# DRV8701E.net
KiCad netlist of a schematic drawn in Altium Designer
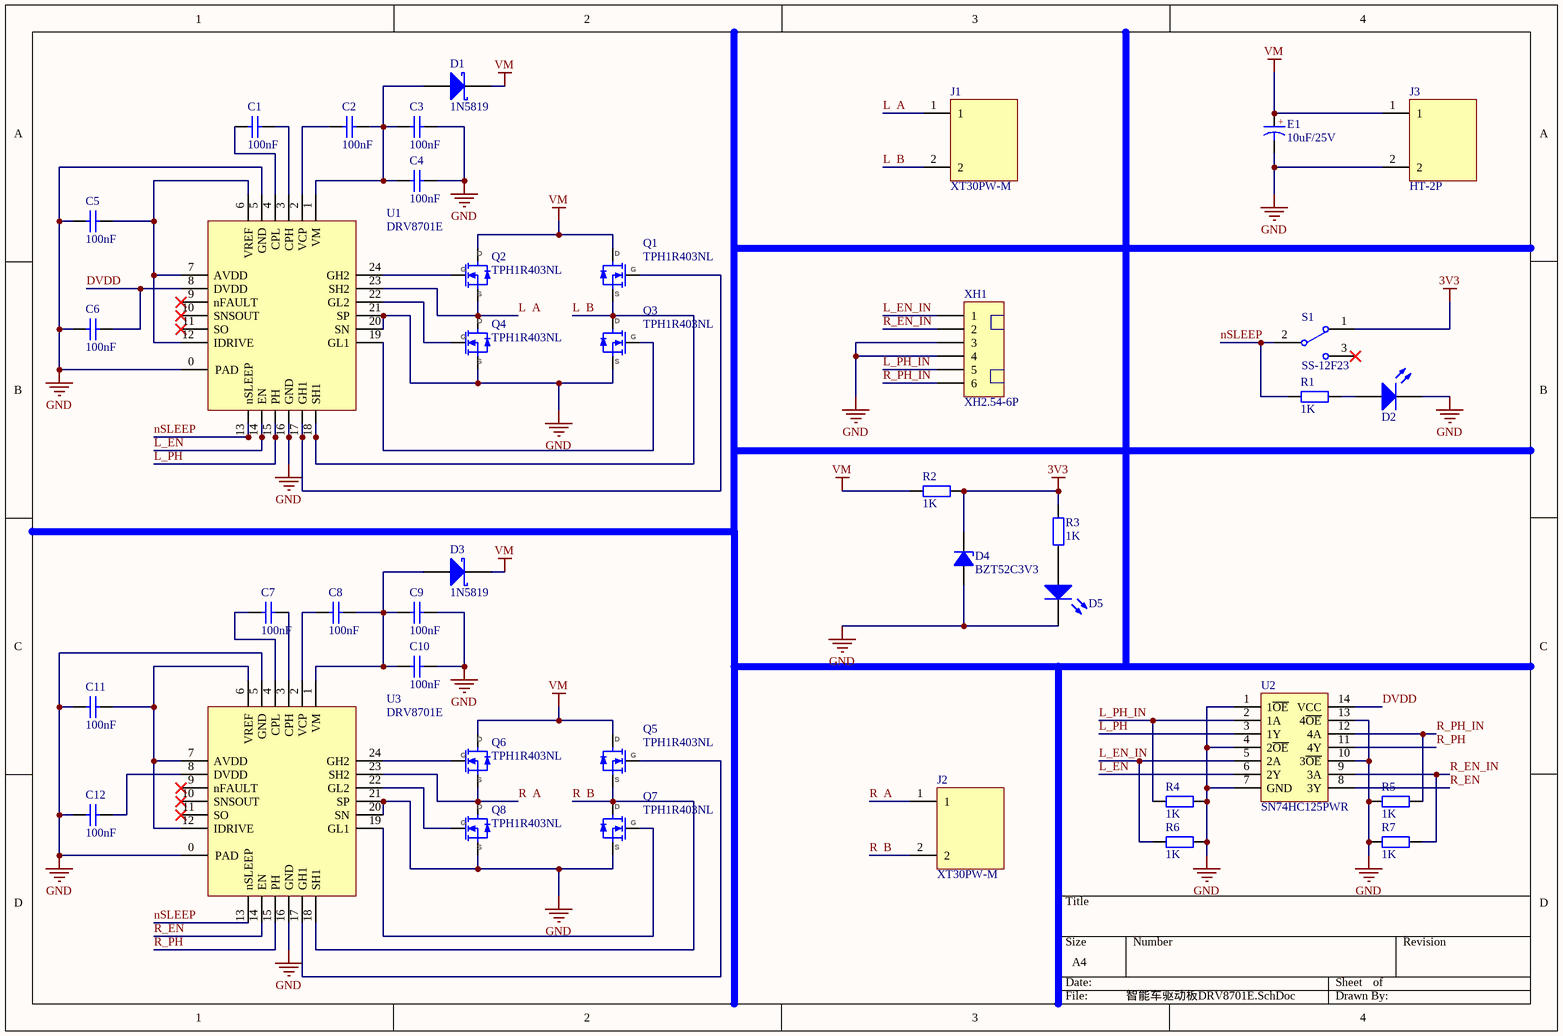
[diagram p0: 智能车驱动板DRV8701E.SchDoc]

(export (version "E")
  (design (tool "Eeschema 10.0.6"))
  (components
    (comp (ref "C1")
      (value "100nF")
      (footprint "C0603_L")
      (description "贴片电容")
      (libsource (lib "0.1_电容&电感&电阻&保险丝") (part "C-SMD"))
    )
    (comp (ref "C2")
      (value "100nF")
      (footprint "C0603_L")
      (description "贴片电容")
      (libsource (lib "0.1_电容&电感&电阻&保险丝") (part "C-SMD"))
    )
    (comp (ref "C3")
      (value "100nF")
      (footprint "C0603_L")
      (description "贴片电容")
      (libsource (lib "0.1_电容&电感&电阻&保险丝") (part "C-SMD"))
    )
    (comp (ref "C4")
      (value "100nF")
      (footprint "C0603_L")
      (description "贴片电容")
      (libsource (lib "0.1_电容&电感&电阻&保险丝") (part "C-SMD"))
    )
    (comp (ref "C5")
      (value "100nF")
      (footprint "C0603_L")
      (description "贴片电容")
      (libsource (lib "0.1_电容&电感&电阻&保险丝") (part "C-SMD"))
    )
    (comp (ref "C6")
      (value "100nF")
      (footprint "C0603_L")
      (description "贴片电容")
      (libsource (lib "0.1_电容&电感&电阻&保险丝") (part "C-SMD"))
    )
    (comp (ref "C7")
      (value "100nF")
      (footprint "C0603_L")
      (description "贴片电容")
      (libsource (lib "0.1_电容&电感&电阻&保险丝") (part "C-SMD"))
    )
    (comp (ref "C8")
      (value "100nF")
      (footprint "C0603_L")
      (description "贴片电容")
      (libsource (lib "0.1_电容&电感&电阻&保险丝") (part "C-SMD"))
    )
    (comp (ref "C9")
      (value "100nF")
      (footprint "C0603_L")
      (description "贴片电容")
      (libsource (lib "0.1_电容&电感&电阻&保险丝") (part "C-SMD"))
    )
    (comp (ref "C10")
      (value "100nF")
      (footprint "C0603_L")
      (description "贴片电容")
      (libsource (lib "0.1_电容&电感&电阻&保险丝") (part "C-SMD"))
    )
    (comp (ref "C11")
      (value "100nF")
      (footprint "C0603_L")
      (description "贴片电容")
      (libsource (lib "0.1_电容&电感&电阻&保险丝") (part "C-SMD"))
    )
    (comp (ref "C12")
      (value "100nF")
      (footprint "C0603_L")
      (description "贴片电容")
      (libsource (lib "0.1_电容&电感&电阻&保险丝") (part "C-SMD"))
    )
    (comp (ref "D1")
      (value "1N5819")
      (footprint "SOD-323")
      (description "肖特基二极管")
      (libsource (lib "0.2_二极管&整流桥") (part "1N5819"))
    )
    (comp (ref "D2")
      (value "LED")
      (footprint "LED-0603_R")
      (description "贴片发光二极管")
      (libsource (lib "0.3_LED发光二极管") (part "LED_SMD"))
    )
    (comp (ref "D3")
      (value "1N5819")
      (footprint "SOD-323")
      (description "肖特基二极管")
      (libsource (lib "0.2_二极管&整流桥") (part "1N5819"))
    )
    (comp (ref "D4")
      (value "BZT52C3V3")
      (footprint "SOD-123-L")
      (description "3.3V稳压二极管")
      (fields (field (name "PUBLISHER") "Altium Limited"))
      (libsource (lib "0.2_二极管&整流桥") (part "Diode Zen"))
    )
    (comp (ref "D5")
      (value "LED")
      (footprint "LED-0603_R")
      (description "贴片发光二极管")
      (libsource (lib "0.3_LED发光二极管") (part "LED_SMD"))
    )
    (comp (ref "E1")
      (value "10uF/25V")
      (footprint "CT-2.0*5*8-R")
      (description "直插固态电容")
      (libsource (lib "0.1_电容&电感&电阻&保险丝") (part "C-CS"))
    )
    (comp (ref "J1")
      (value "XT30PW-M")
      (footprint "XT30-WI")
      (description "30A Low Temperature Rise Fire Retardant Plug")
      (libsource (lib "5.12_XT30&XT60") (part "XT30PW-M"))
    )
    (comp (ref "J2")
      (value "XT30PW-M")
      (footprint "XT30-WI")
      (description "30A Low Temperature Rise Fire Retardant Plug")
      (libsource (lib "5.12_XT30&XT60") (part "XT30PW-M"))
    )
    (comp (ref "J3")
      (value "HT-2P")
      (footprint "CZ-5.08-L-Z-2P")
      (description "30A Low Temperature Rise Fire Retardant Plug")
      (fields (field (name "MANUFACTURER_PART_NUMBER") "XT30PW-M"))
      (libsource (lib "5.12_XT30&XT60") (part "XT30PW-M"))
    )
    (comp (ref "Q1")
      (value "TPH1R403NL")
      (footprint "DFN5x6")
      (description "N沟道MOS")
      (libsource (lib "0.4_场效应管&可控硅") (part "TPH1R403NL"))
    )
    (comp (ref "Q2")
      (value "TPH1R403NL")
      (footprint "DFN5x6")
      (description "N沟道MOS")
      (libsource (lib "0.4_场效应管&可控硅") (part "TPH1R403NL"))
    )
    (comp (ref "Q3")
      (value "TPH1R403NL")
      (footprint "DFN5x6")
      (description "N沟道MOS")
      (libsource (lib "0.4_场效应管&可控硅") (part "TPH1R403NL"))
    )
    (comp (ref "Q4")
      (value "TPH1R403NL")
      (footprint "DFN5x6")
      (description "N沟道MOS")
      (libsource (lib "0.4_场效应管&可控硅") (part "TPH1R403NL"))
    )
    (comp (ref "Q5")
      (value "TPH1R403NL")
      (footprint "DFN5x6")
      (description "N沟道MOS")
      (libsource (lib "0.4_场效应管&可控硅") (part "TPH1R403NL"))
    )
    (comp (ref "Q6")
      (value "TPH1R403NL")
      (footprint "DFN5x6")
      (description "N沟道MOS")
      (libsource (lib "0.4_场效应管&可控硅") (part "TPH1R403NL"))
    )
    (comp (ref "Q7")
      (value "TPH1R403NL")
      (footprint "DFN5x6")
      (description "N沟道MOS")
      (libsource (lib "0.4_场效应管&可控硅") (part "TPH1R403NL"))
    )
    (comp (ref "Q8")
      (value "TPH1R403NL")
      (footprint "DFN5x6")
      (description "N沟道MOS")
      (libsource (lib "0.4_场效应管&可控硅") (part "TPH1R403NL"))
    )
    (comp (ref "R1")
      (value "1K")
      (footprint "R0603_L")
      (description "贴片电阻")
      (libsource (lib "0.1_电容&电感&电阻&保险丝") (part "R-SMD"))
    )
    (comp (ref "R2")
      (value "1K")
      (footprint "R0603_L")
      (description "贴片电阻")
      (libsource (lib "0.1_电容&电感&电阻&保险丝") (part "R-SMD"))
    )
    (comp (ref "R3")
      (value "1K")
      (footprint "R0603_L")
      (description "贴片电阻")
      (libsource (lib "0.1_电容&电感&电阻&保险丝") (part "R-SMD"))
    )
    (comp (ref "R4")
      (value "1K")
      (footprint "R0603_L")
      (description "贴片电阻")
      (libsource (lib "0.1_电容&电感&电阻&保险丝") (part "R-SMD"))
    )
    (comp (ref "R5")
      (value "1K")
      (footprint "R0603_L")
      (description "贴片电阻")
      (libsource (lib "0.1_电容&电感&电阻&保险丝") (part "R-SMD"))
    )
    (comp (ref "R6")
      (value "1K")
      (footprint "R0603_L")
      (description "贴片电阻")
      (libsource (lib "0.1_电容&电感&电阻&保险丝") (part "R-SMD"))
    )
    (comp (ref "R7")
      (value "1K")
      (footprint "R0603_L")
      (description "贴片电阻")
      (libsource (lib "0.1_电容&电感&电阻&保险丝") (part "R-SMD"))
    )
    (comp (ref "S1")
      (value "SS-12F23")
      (footprint "MSK-12C01-07")
      (description "1路波动开关")
      (libsource (lib "0.8_按键&开关") (part "SSW-1P"))
    )
    (comp (ref "U1")
      (value "DRV8701E")
      (footprint "QFN24-4x4")
      (description "DRV8701E Ti全桥驱动芯片")
      (libsource (lib "1.3_电机驱动芯片") (part "DRV8701E"))
    )
    (comp (ref "U2")
      (value "SN74HC125PWR")
      (footprint "TSSOP14")
      (description "三态输出的四路缓冲器")
      (libsource (lib "1.7_隔离类芯片") (part "SN74HC125PWR"))
    )
    (comp (ref "U3")
      (value "DRV8701E")
      (footprint "QFN24-4x4")
      (description "DRV8701E Ti全桥驱动芯片")
      (libsource (lib "1.3_电机驱动芯片") (part "DRV8701E"))
    )
    (comp (ref "XH1")
      (value "XH2.54-6P")
      (footprint "XH2.54-6P-WI")
      (libsource (lib "5.2_XH") (part "XH2.54-6P"))
    )
  )
  (nets
    (net (code "1") (name "/DVDD") (class "Default")
      (node (ref "C6") (pin "2") (pinfunction "2_2") (pintype "passive"))
      (node (ref "U1") (pin "8") (pinfunction "DVDD_8") (pintype "passive"))
      (node (ref "U2") (pin "14") (pinfunction "VCC_14") (pintype "passive"))
    )
    (net (code "2") (name "/L  A") (class "Default")
      (node (ref "J1") (pin "1") (pinfunction "1_1") (pintype "passive"))
      (node (ref "Q2") (pin "3") (pinfunction "S_3") (pintype "passive"))
      (node (ref "Q4") (pin "1") (pinfunction "D_1") (pintype "passive"))
      (node (ref "U1") (pin "23") (pinfunction "SH2_23") (pintype "passive"))
    )
    (net (code "3") (name "/L  B") (class "Default")
      (node (ref "J1") (pin "2") (pinfunction "2_2") (pintype "passive"))
      (node (ref "Q1") (pin "3") (pinfunction "S_3") (pintype "passive"))
      (node (ref "Q3") (pin "1") (pinfunction "D_1") (pintype "passive"))
      (node (ref "U1") (pin "18") (pinfunction "SH1_18") (pintype "passive"))
    )
    (net (code "4") (name "/L_EN") (class "Default")
      (node (ref "U1") (pin "14") (pinfunction "EN_14") (pintype "passive"))
      (node (ref "U2") (pin "6") (pinfunction "2Y_6") (pintype "passive"))
    )
    (net (code "5") (name "/L_EN_IN") (class "Default")
      (node (ref "R6") (pin "1") (pinfunction "1_1") (pintype "passive"))
      (node (ref "U2") (pin "5") (pinfunction "2A_5") (pintype "passive"))
      (node (ref "XH1") (pin "1") (pinfunction "1_1") (pintype "passive"))
    )
    (net (code "6") (name "/L_PH") (class "Default")
      (node (ref "U1") (pin "15") (pinfunction "PH_15") (pintype "passive"))
      (node (ref "U2") (pin "3") (pinfunction "1Y_3") (pintype "passive"))
    )
    (net (code "7") (name "/L_PH_IN") (class "Default")
      (node (ref "R4") (pin "1") (pinfunction "1_1") (pintype "passive"))
      (node (ref "U2") (pin "2") (pinfunction "1A_2") (pintype "passive"))
      (node (ref "XH1") (pin "5") (pinfunction "5_5") (pintype "passive"))
    )
    (net (code "8") (name "/R  A") (class "Default")
      (node (ref "J2") (pin "1") (pinfunction "1_1") (pintype "passive"))
      (node (ref "Q6") (pin "3") (pinfunction "S_3") (pintype "passive"))
      (node (ref "Q8") (pin "1") (pinfunction "D_1") (pintype "passive"))
      (node (ref "U3") (pin "23") (pinfunction "SH2_23") (pintype "passive"))
    )
    (net (code "9") (name "/R  B") (class "Default")
      (node (ref "J2") (pin "2") (pinfunction "2_2") (pintype "passive"))
      (node (ref "Q5") (pin "3") (pinfunction "S_3") (pintype "passive"))
      (node (ref "Q7") (pin "1") (pinfunction "D_1") (pintype "passive"))
      (node (ref "U3") (pin "18") (pinfunction "SH1_18") (pintype "passive"))
    )
    (net (code "10") (name "/R_EN") (class "Default")
      (node (ref "U2") (pin "8") (pinfunction "3Y_8") (pintype "passive"))
      (node (ref "U3") (pin "14") (pinfunction "EN_14") (pintype "passive"))
    )
    (net (code "11") (name "/R_EN_IN") (class "Default")
      (node (ref "R7") (pin "2") (pinfunction "2_2") (pintype "passive"))
      (node (ref "U2") (pin "9") (pinfunction "3A_9") (pintype "passive"))
      (node (ref "XH1") (pin "2") (pinfunction "2_2") (pintype "passive"))
    )
    (net (code "12") (name "/R_PH") (class "Default")
      (node (ref "U2") (pin "11") (pinfunction "4Y_11") (pintype "passive"))
      (node (ref "U3") (pin "15") (pinfunction "PH_15") (pintype "passive"))
    )
    (net (code "13") (name "/R_PH_IN") (class "Default")
      (node (ref "R5") (pin "2") (pinfunction "2_2") (pintype "passive"))
      (node (ref "U2") (pin "12") (pinfunction "4A_12") (pintype "passive"))
      (node (ref "XH1") (pin "6") (pinfunction "6_6") (pintype "passive"))
    )
    (net (code "14") (name "/nSLEEP") (class "Default")
      (node (ref "R1") (pin "1") (pinfunction "1_1") (pintype "passive"))
      (node (ref "S1") (pin "2") (pinfunction "2_2") (pintype "passive"))
      (node (ref "U1") (pin "13") (pinfunction "nSLEEP_13") (pintype "passive"))
      (node (ref "U3") (pin "13") (pinfunction "nSLEEP_13") (pintype "passive"))
    )
    (net (code "15") (name "3V3") (class "Default")
      (node (ref "D4") (pin "K") (pinfunction "K_K") (pintype "passive"))
      (node (ref "R2") (pin "2") (pinfunction "2_2") (pintype "passive"))
      (node (ref "R3") (pin "2") (pinfunction "2_2") (pintype "passive"))
      (node (ref "S1") (pin "1") (pinfunction "1_1") (pintype "passive"))
    )
    (net (code "16") (name "GND") (class "Default")
      (node (ref "C10") (pin "2") (pinfunction "2_2") (pintype "passive"))
      (node (ref "C11") (pin "1") (pinfunction "1_1") (pintype "passive"))
      (node (ref "C12") (pin "1") (pinfunction "1_1") (pintype "passive"))
      (node (ref "C3") (pin "2") (pinfunction "2_2") (pintype "passive"))
      (node (ref "C4") (pin "2") (pinfunction "2_2") (pintype "passive"))
      (node (ref "C5") (pin "1") (pinfunction "1_1") (pintype "passive"))
      (node (ref "C6") (pin "1") (pinfunction "1_1") (pintype "passive"))
      (node (ref "C9") (pin "2") (pinfunction "2_2") (pintype "passive"))
      (node (ref "D2") (pin "2") (pinfunction "K_2") (pintype "passive"))
      (node (ref "D4") (pin "A") (pinfunction "A_A") (pintype "passive"))
      (node (ref "D5") (pin "2") (pinfunction "K_2") (pintype "passive"))
      (node (ref "E1") (pin "2") (pinfunction "2_2") (pintype "passive"))
      (node (ref "J3") (pin "2") (pinfunction "2_2") (pintype "passive"))
      (node (ref "Q3") (pin "3") (pinfunction "S_3") (pintype "passive"))
      (node (ref "Q4") (pin "3") (pinfunction "S_3") (pintype "passive"))
      (node (ref "Q7") (pin "3") (pinfunction "S_3") (pintype "passive"))
      (node (ref "Q8") (pin "3") (pinfunction "S_3") (pintype "passive"))
      (node (ref "R4") (pin "2") (pinfunction "2_2") (pintype "passive"))
      (node (ref "R5") (pin "1") (pinfunction "1_1") (pintype "passive"))
      (node (ref "R6") (pin "2") (pinfunction "2_2") (pintype "passive"))
      (node (ref "R7") (pin "1") (pinfunction "1_1") (pintype "passive"))
      (node (ref "U1") (pin "0") (pinfunction "PAD_0") (pintype "passive"))
      (node (ref "U1") (pin "16") (pinfunction "GND_16") (pintype "passive"))
      (node (ref "U1") (pin "20") (pinfunction "SN_20") (pintype "passive"))
      (node (ref "U1") (pin "21") (pinfunction "SP_21") (pintype "passive"))
      (node (ref "U1") (pin "5") (pinfunction "GND_5") (pintype "passive"))
      (node (ref "U2") (pin "1") (pinfunction "1~{OE}_1") (pintype "passive"))
      (node (ref "U2") (pin "10") (pinfunction "3~{OE}_10") (pintype "passive"))
      (node (ref "U2") (pin "13") (pinfunction "4~{OE}_13") (pintype "passive"))
      (node (ref "U2") (pin "4") (pinfunction "2~{OE}_4") (pintype "passive"))
      (node (ref "U2") (pin "7") (pinfunction "GND_7") (pintype "passive"))
      (node (ref "U3") (pin "0") (pinfunction "PAD_0") (pintype "passive"))
      (node (ref "U3") (pin "16") (pinfunction "GND_16") (pintype "passive"))
      (node (ref "U3") (pin "20") (pinfunction "SN_20") (pintype "passive"))
      (node (ref "U3") (pin "21") (pinfunction "SP_21") (pintype "passive"))
      (node (ref "U3") (pin "5") (pinfunction "GND_5") (pintype "passive"))
      (node (ref "XH1") (pin "3") (pinfunction "3_3") (pintype "passive"))
      (node (ref "XH1") (pin "4") (pinfunction "4_4") (pintype "passive"))
    )
    (net (code "17") (name "Net-(D1-A)") (class "Default")
      (node (ref "C2") (pin "2") (pinfunction "2_2") (pintype "passive"))
      (node (ref "C3") (pin "1") (pinfunction "1_1") (pintype "passive"))
      (node (ref "C4") (pin "1") (pinfunction "1_1") (pintype "passive"))
      (node (ref "D1") (pin "1") (pinfunction "A_1") (pintype "passive"))
      (node (ref "U1") (pin "1") (pinfunction "VM_1") (pintype "passive"))
    )
    (net (code "18") (name "Net-(D2-A)") (class "Default")
      (node (ref "D2") (pin "1") (pinfunction "A_1") (pintype "passive"))
      (node (ref "R1") (pin "2") (pinfunction "2_2") (pintype "passive"))
    )
    (net (code "19") (name "Net-(D3-A)") (class "Default")
      (node (ref "C10") (pin "1") (pinfunction "1_1") (pintype "passive"))
      (node (ref "C8") (pin "2") (pinfunction "2_2") (pintype "passive"))
      (node (ref "C9") (pin "1") (pinfunction "1_1") (pintype "passive"))
      (node (ref "D3") (pin "1") (pinfunction "A_1") (pintype "passive"))
      (node (ref "U3") (pin "1") (pinfunction "VM_1") (pintype "passive"))
    )
    (net (code "20") (name "Net-(D5-A)") (class "Default")
      (node (ref "D5") (pin "1") (pinfunction "A_1") (pintype "passive"))
      (node (ref "R3") (pin "1") (pinfunction "1_1") (pintype "passive"))
    )
    (net (code "21") (name "Net-(Q1-G)") (class "Default")
      (node (ref "Q1") (pin "2") (pinfunction "G_2") (pintype "passive"))
      (node (ref "U1") (pin "17") (pinfunction "GH1_17") (pintype "passive"))
    )
    (net (code "22") (name "Net-(Q2-G)") (class "Default")
      (node (ref "Q2") (pin "2") (pinfunction "G_2") (pintype "passive"))
      (node (ref "U1") (pin "24") (pinfunction "GH2_24") (pintype "passive"))
    )
    (net (code "23") (name "Net-(Q3-G)") (class "Default")
      (node (ref "Q3") (pin "2") (pinfunction "G_2") (pintype "passive"))
      (node (ref "U1") (pin "19") (pinfunction "GL1_19") (pintype "passive"))
    )
    (net (code "24") (name "Net-(Q4-G)") (class "Default")
      (node (ref "Q4") (pin "2") (pinfunction "G_2") (pintype "passive"))
      (node (ref "U1") (pin "22") (pinfunction "GL2_22") (pintype "passive"))
    )
    (net (code "25") (name "Net-(Q5-G)") (class "Default")
      (node (ref "Q5") (pin "2") (pinfunction "G_2") (pintype "passive"))
      (node (ref "U3") (pin "17") (pinfunction "GH1_17") (pintype "passive"))
    )
    (net (code "26") (name "Net-(Q6-G)") (class "Default")
      (node (ref "Q6") (pin "2") (pinfunction "G_2") (pintype "passive"))
      (node (ref "U3") (pin "24") (pinfunction "GH2_24") (pintype "passive"))
    )
    (net (code "27") (name "Net-(Q7-G)") (class "Default")
      (node (ref "Q7") (pin "2") (pinfunction "G_2") (pintype "passive"))
      (node (ref "U3") (pin "19") (pinfunction "GL1_19") (pintype "passive"))
    )
    (net (code "28") (name "Net-(Q8-G)") (class "Default")
      (node (ref "Q8") (pin "2") (pinfunction "G_2") (pintype "passive"))
      (node (ref "U3") (pin "22") (pinfunction "GL2_22") (pintype "passive"))
    )
    (net (code "29") (name "Net-(U1-AVDD)") (class "Default")
      (node (ref "C5") (pin "2") (pinfunction "2_2") (pintype "passive"))
      (node (ref "U1") (pin "12") (pinfunction "IDRIVE_12") (pintype "passive"))
      (node (ref "U1") (pin "6") (pinfunction "VREF_6") (pintype "passive"))
      (node (ref "U1") (pin "7") (pinfunction "AVDD_7") (pintype "passive"))
    )
    (net (code "30") (name "Net-(U1-CPH)") (class "Default")
      (node (ref "C1") (pin "2") (pinfunction "2_2") (pintype "passive"))
      (node (ref "U1") (pin "3") (pinfunction "CPH_3") (pintype "passive"))
    )
    (net (code "31") (name "Net-(U1-CPL)") (class "Default")
      (node (ref "C1") (pin "1") (pinfunction "1_1") (pintype "passive"))
      (node (ref "U1") (pin "4") (pinfunction "CPL_4") (pintype "passive"))
    )
    (net (code "32") (name "Net-(U1-VCP)") (class "Default")
      (node (ref "C2") (pin "1") (pinfunction "1_1") (pintype "passive"))
      (node (ref "U1") (pin "2") (pinfunction "VCP_2") (pintype "passive"))
    )
    (net (code "33") (name "Net-(U3-AVDD)") (class "Default")
      (node (ref "C11") (pin "2") (pinfunction "2_2") (pintype "passive"))
      (node (ref "U3") (pin "12") (pinfunction "IDRIVE_12") (pintype "passive"))
      (node (ref "U3") (pin "6") (pinfunction "VREF_6") (pintype "passive"))
      (node (ref "U3") (pin "7") (pinfunction "AVDD_7") (pintype "passive"))
    )
    (net (code "34") (name "Net-(U3-CPH)") (class "Default")
      (node (ref "C7") (pin "2") (pinfunction "2_2") (pintype "passive"))
      (node (ref "U3") (pin "3") (pinfunction "CPH_3") (pintype "passive"))
    )
    (net (code "35") (name "Net-(U3-CPL)") (class "Default")
      (node (ref "C7") (pin "1") (pinfunction "1_1") (pintype "passive"))
      (node (ref "U3") (pin "4") (pinfunction "CPL_4") (pintype "passive"))
    )
    (net (code "36") (name "Net-(U3-DVDD)") (class "Default")
      (node (ref "C12") (pin "2") (pinfunction "2_2") (pintype "passive"))
      (node (ref "U3") (pin "8") (pinfunction "DVDD_8") (pintype "passive"))
    )
    (net (code "37") (name "Net-(U3-VCP)") (class "Default")
      (node (ref "C8") (pin "1") (pinfunction "1_1") (pintype "passive"))
      (node (ref "U3") (pin "2") (pinfunction "VCP_2") (pintype "passive"))
    )
    (net (code "38") (name "VM") (class "Default")
      (node (ref "D1") (pin "2") (pinfunction "K_2") (pintype "passive"))
      (node (ref "D3") (pin "2") (pinfunction "K_2") (pintype "passive"))
      (node (ref "E1") (pin "1") (pinfunction "1_1") (pintype "passive"))
      (node (ref "J3") (pin "1") (pinfunction "1_1") (pintype "passive"))
      (node (ref "Q1") (pin "1") (pinfunction "D_1") (pintype "passive"))
      (node (ref "Q2") (pin "1") (pinfunction "D_1") (pintype "passive"))
      (node (ref "Q5") (pin "1") (pinfunction "D_1") (pintype "passive"))
      (node (ref "Q6") (pin "1") (pinfunction "D_1") (pintype "passive"))
      (node (ref "R2") (pin "1") (pinfunction "1_1") (pintype "passive"))
    )
    (net (code "39") (name "unconnected-(S1-Pad3)") (class "Default")
      (node (ref "S1") (pin "3") (pinfunction "3_3") (pintype "passive+no_connect"))
    )
    (net (code "40") (name "unconnected-(U1-SNSOUT-Pad10)") (class "Default")
      (node (ref "U1") (pin "10") (pinfunction "SNSOUT_10") (pintype "passive+no_connect"))
    )
    (net (code "41") (name "unconnected-(U1-SO-Pad11)") (class "Default")
      (node (ref "U1") (pin "11") (pinfunction "SO_11") (pintype "passive+no_connect"))
    )
    (net (code "42") (name "unconnected-(U1-nFAULT-Pad9)") (class "Default")
      (node (ref "U1") (pin "9") (pinfunction "nFAULT_9") (pintype "passive+no_connect"))
    )
    (net (code "43") (name "unconnected-(U3-SNSOUT-Pad10)") (class "Default")
      (node (ref "U3") (pin "10") (pinfunction "SNSOUT_10") (pintype "passive+no_connect"))
    )
    (net (code "44") (name "unconnected-(U3-SO-Pad11)") (class "Default")
      (node (ref "U3") (pin "11") (pinfunction "SO_11") (pintype "passive+no_connect"))
    )
    (net (code "45") (name "unconnected-(U3-nFAULT-Pad9)") (class "Default")
      (node (ref "U3") (pin "9") (pinfunction "nFAULT_9") (pintype "passive+no_connect"))
    )
  )
)
